# DAB_FM_Radio.net
KiCad netlist of a schematic drawn in EAGLE
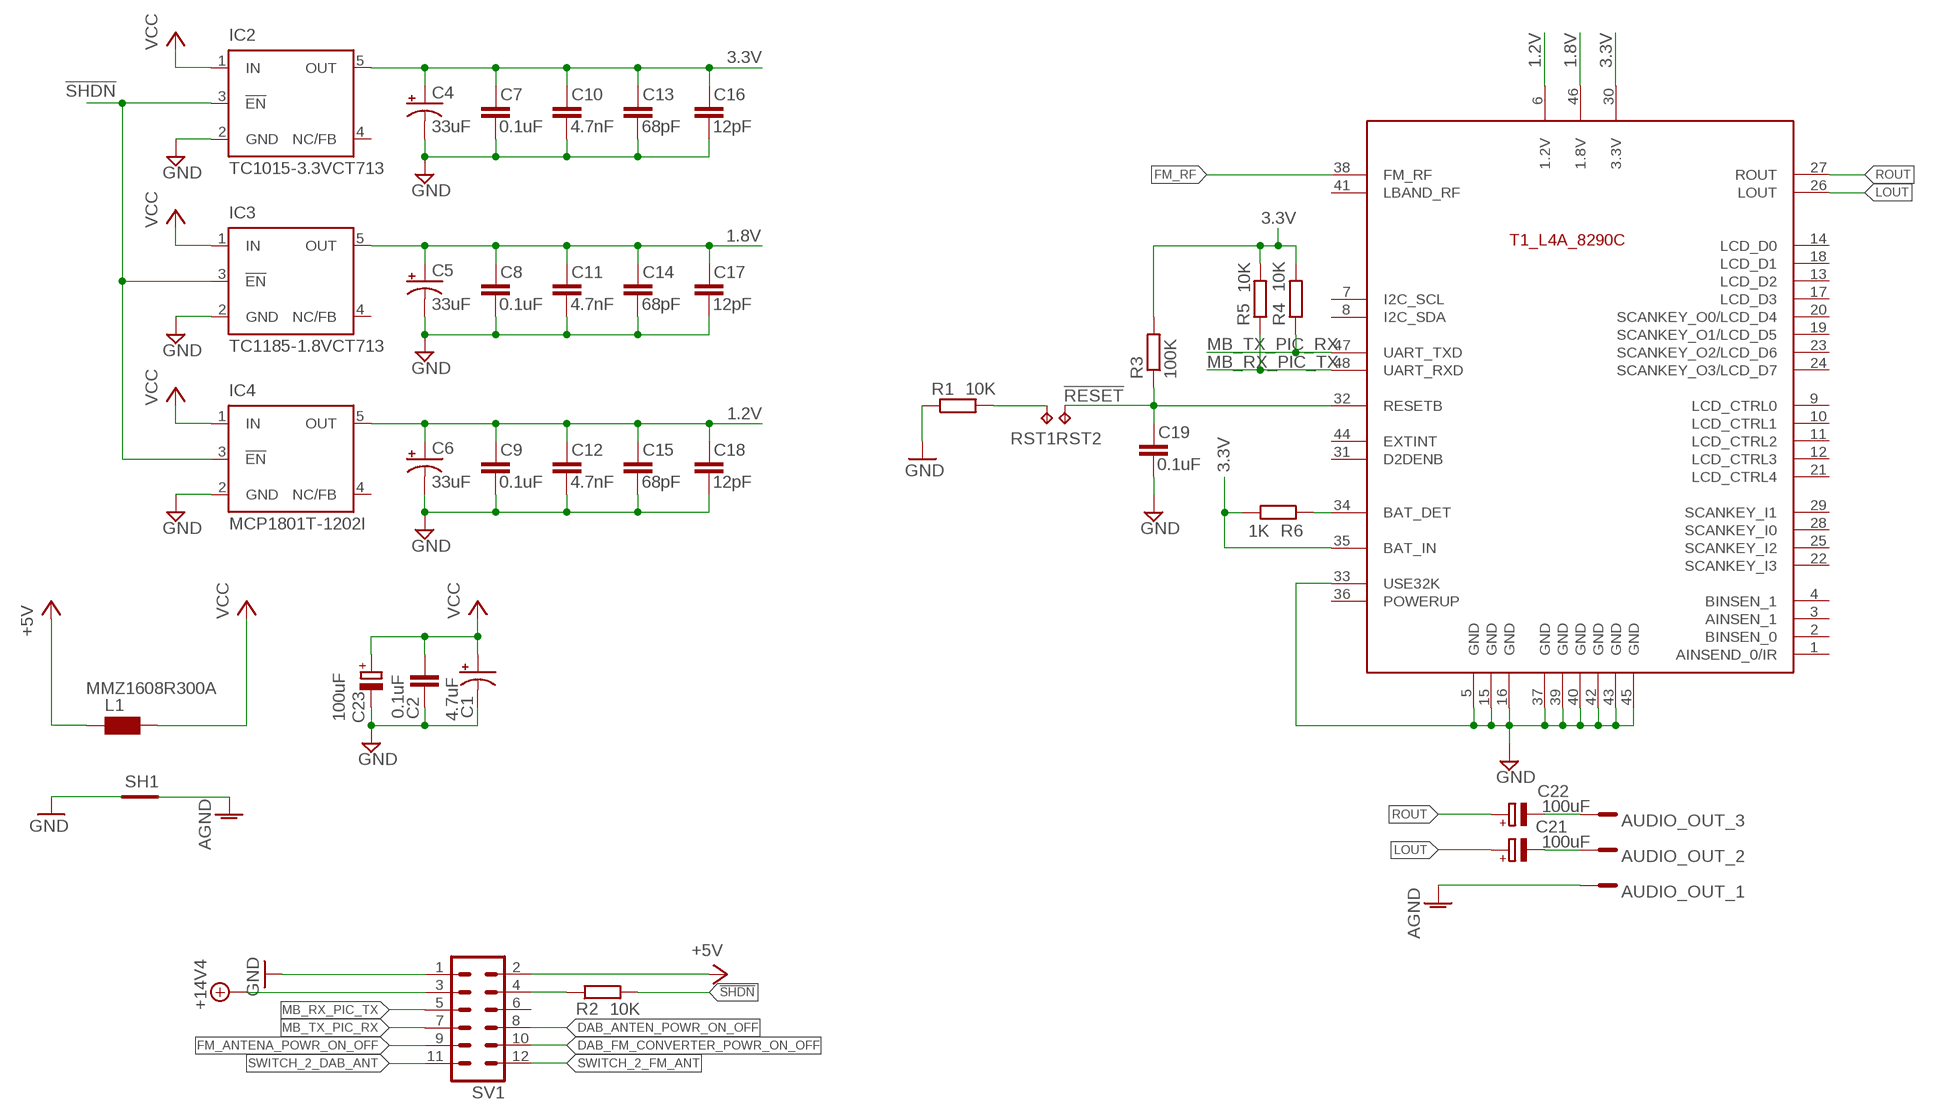
[diagram p0: schematic, sheet 1, part 1 of 2]
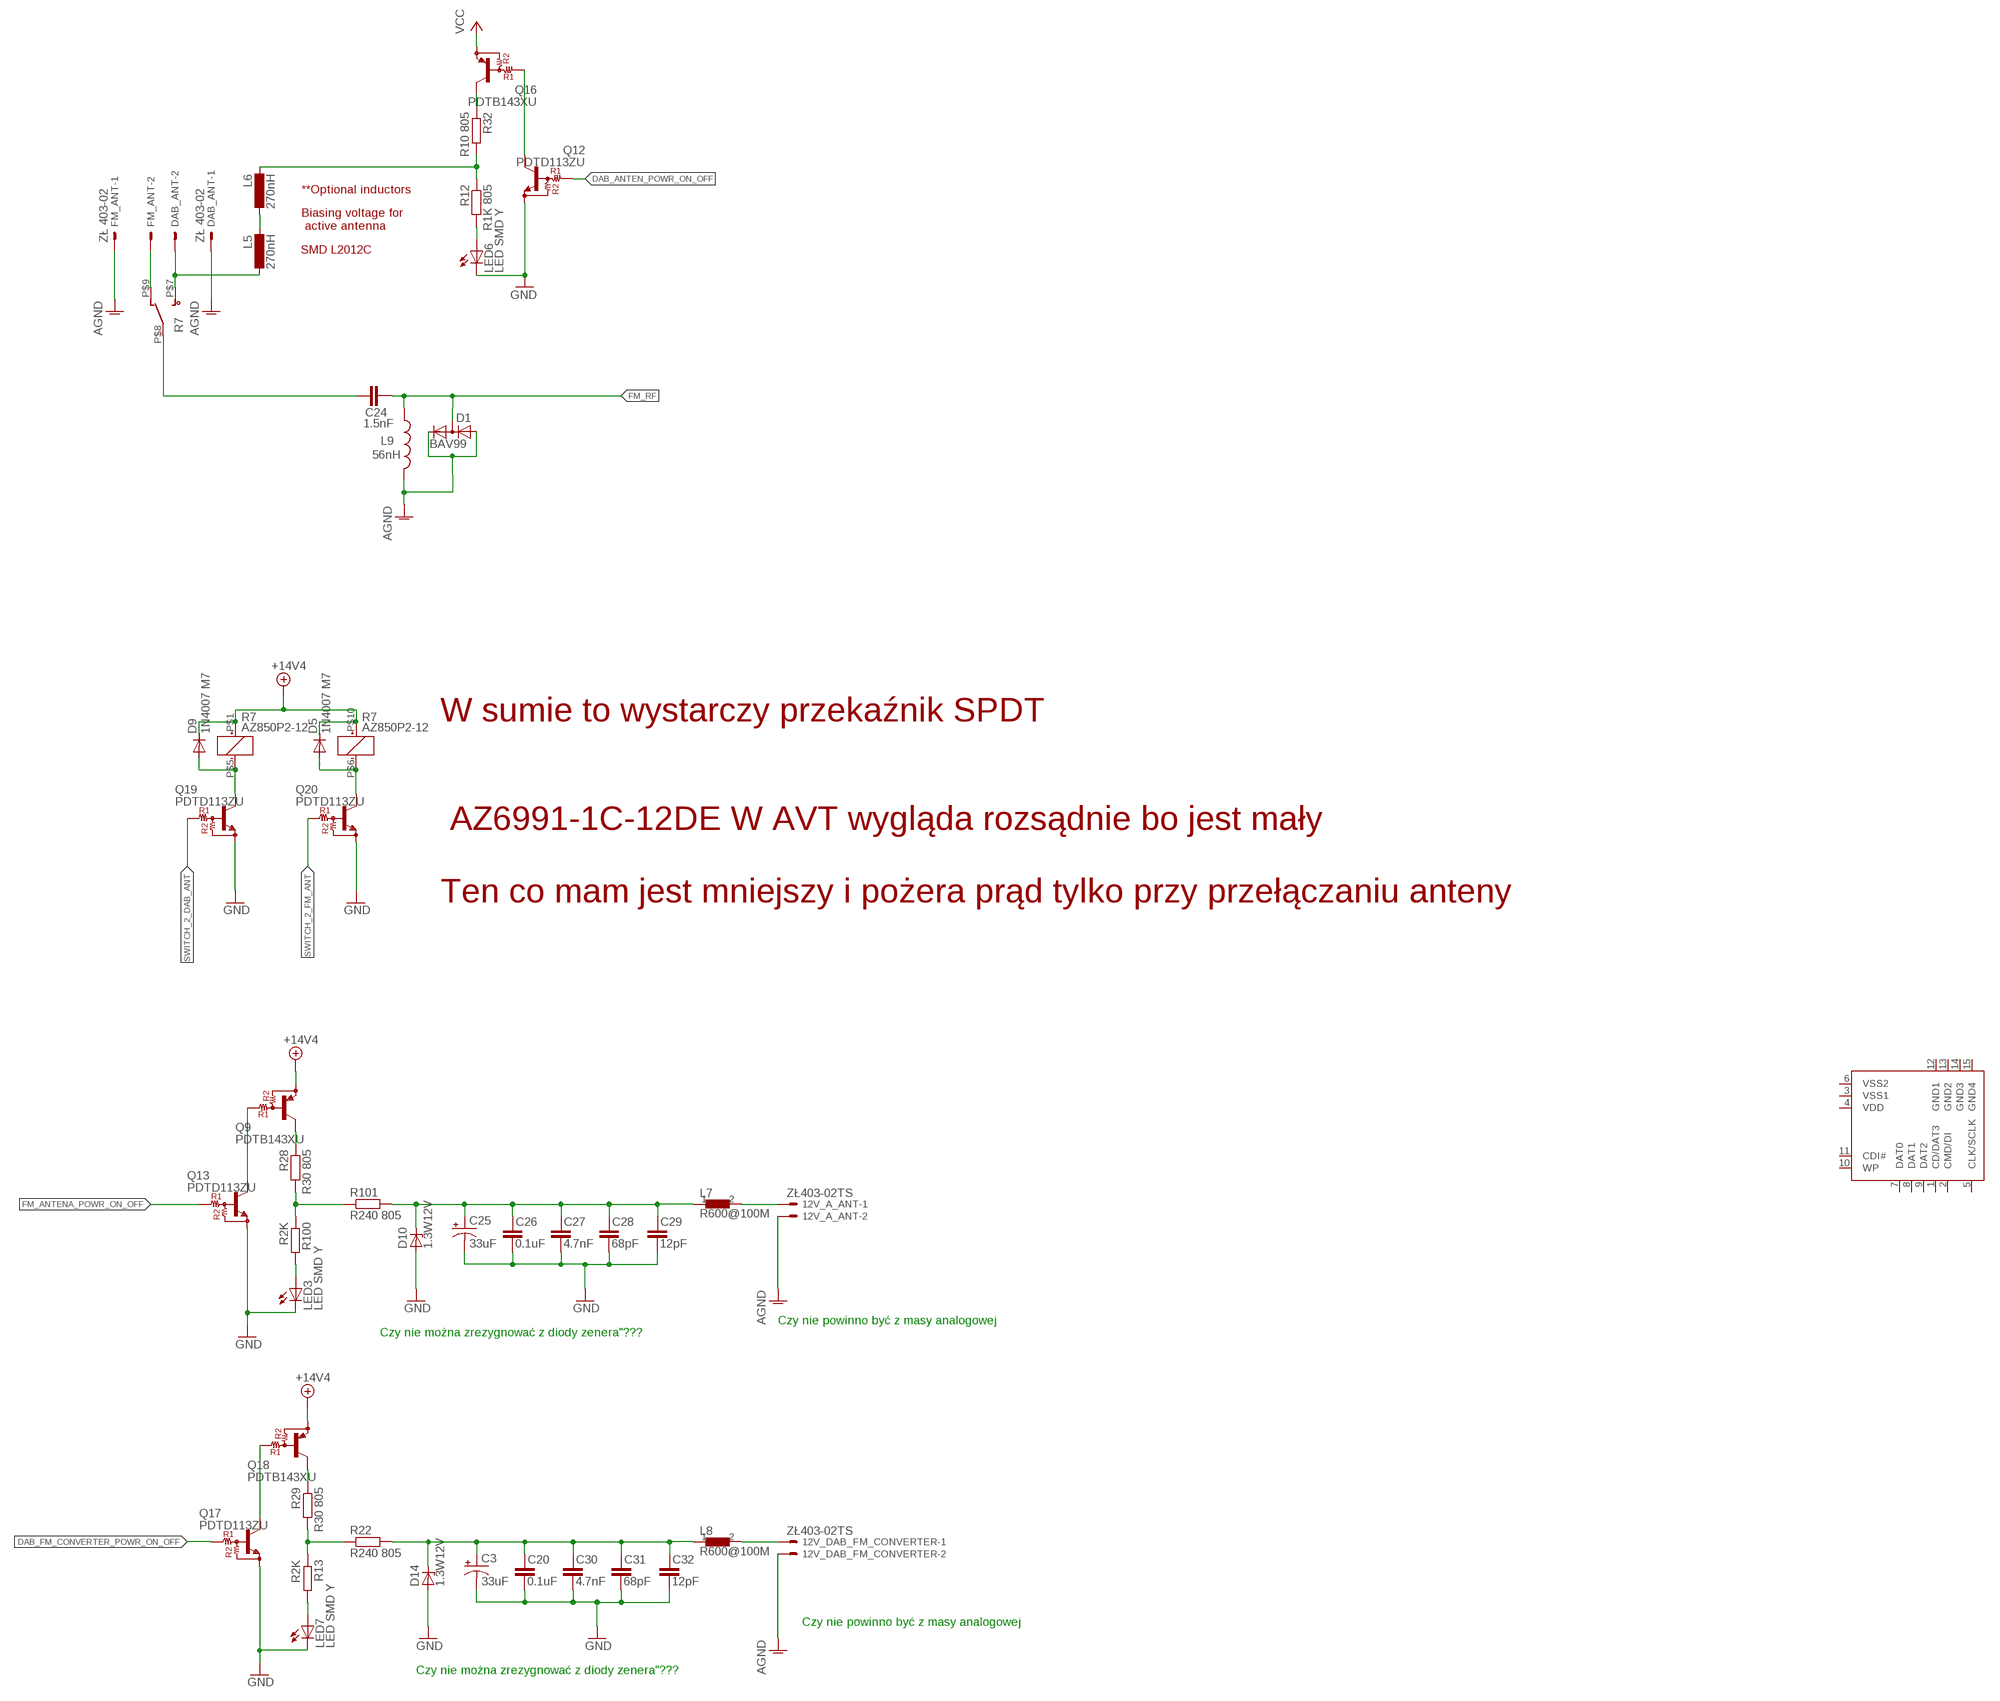
[diagram p1: schematic, sheet 1, part 2 of 2]

(export (version "E")
  (design (tool "Eeschema 10.0.6"))
  (components
    (comp (ref "12V_A_ANT")
      (value "ZŁ403-02TS")
      (footprint "eagle-import:22-23-2021")
      (fields (field (name "MF") "MOLEX") (field (name "MPN") "22-23-2021"))
      (libsource (lib "eagle-import") (part "22-23-2021"))
    )
    (comp (ref "12V_DAB_FM_CONVERTER")
      (value "ZŁ403-02TS")
      (footprint "eagle-import:22-23-2021")
      (fields (field (name "MF") "MOLEX") (field (name "MPN") "22-23-2021"))
      (libsource (lib "eagle-import") (part "22-23-2021"))
    )
    (comp (ref "AUDIO_OUT")
      (value "JST_3_PIN_B3B-PH-KS")
      (footprint "eagle-import:B3B-PH-KS")
      (libsource (lib "eagle-import") (part "JST_3_PIN_B3B-PH-KS"))
    )
    (comp (ref "C1")
      (value "4.7uF")
      (footprint "eagle-import:EIA3216")
      (libsource (lib "eagle-import") (part "CAP_POL1206"))
    )
    (comp (ref "C2")
      (value "0.1uF")
      (footprint "eagle-import:C0603")
      (libsource (lib "eagle-import") (part "C-EUC0603"))
    )
    (comp (ref "C3")
      (value "33uF")
      (footprint "eagle-import:EIA3216")
      (libsource (lib "eagle-import") (part "CAP_POL1206"))
    )
    (comp (ref "C4")
      (value "33uF")
      (footprint "eagle-import:EIA3216")
      (libsource (lib "eagle-import") (part "CAP_POL1206"))
    )
    (comp (ref "C5")
      (value "33uF")
      (footprint "eagle-import:EIA3216")
      (libsource (lib "eagle-import") (part "CAP_POL1206"))
    )
    (comp (ref "C6")
      (value "33uF")
      (footprint "eagle-import:EIA3216")
      (libsource (lib "eagle-import") (part "CAP_POL1206"))
    )
    (comp (ref "C7")
      (value "0.1uF")
      (footprint "eagle-import:C0603")
      (libsource (lib "eagle-import") (part "C-EUC0603"))
    )
    (comp (ref "C8")
      (value "0.1uF")
      (footprint "eagle-import:C0603")
      (libsource (lib "eagle-import") (part "C-EUC0603"))
    )
    (comp (ref "C9")
      (value "0.1uF")
      (footprint "eagle-import:C0603")
      (libsource (lib "eagle-import") (part "C-EUC0603"))
    )
    (comp (ref "C10")
      (value "4.7nF")
      (footprint "eagle-import:C0603")
      (libsource (lib "eagle-import") (part "C-EUC0603"))
    )
    (comp (ref "C11")
      (value "4.7nF")
      (footprint "eagle-import:C0603")
      (libsource (lib "eagle-import") (part "C-EUC0603"))
    )
    (comp (ref "C12")
      (value "4.7nF")
      (footprint "eagle-import:C0603")
      (libsource (lib "eagle-import") (part "C-EUC0603"))
    )
    (comp (ref "C13")
      (value "68pF")
      (footprint "eagle-import:C0603")
      (libsource (lib "eagle-import") (part "C-EUC0603"))
    )
    (comp (ref "C14")
      (value "68pF")
      (footprint "eagle-import:C0603")
      (libsource (lib "eagle-import") (part "C-EUC0603"))
    )
    (comp (ref "C15")
      (value "68pF")
      (footprint "eagle-import:C0603")
      (libsource (lib "eagle-import") (part "C-EUC0603"))
    )
    (comp (ref "C16")
      (value "12pF")
      (footprint "eagle-import:C0603")
      (libsource (lib "eagle-import") (part "C-EUC0603"))
    )
    (comp (ref "C17")
      (value "12pF")
      (footprint "eagle-import:C0603")
      (libsource (lib "eagle-import") (part "C-EUC0603"))
    )
    (comp (ref "C18")
      (value "12pF")
      (footprint "eagle-import:C0603")
      (libsource (lib "eagle-import") (part "C-EUC0603"))
    )
    (comp (ref "C19")
      (value "0.1uF")
      (footprint "eagle-import:C0603")
      (libsource (lib "eagle-import") (part "C-EUC0603"))
    )
    (comp (ref "C20")
      (value "0.1uF")
      (footprint "eagle-import:C0603")
      (libsource (lib "eagle-import") (part "C-EUC0603"))
    )
    (comp (ref "C21")
      (value "100uF")
      (footprint "eagle-import:PANASONIC_D")
      (libsource (lib "eagle-import") (part "CPOL-EUD"))
    )
    (comp (ref "C22")
      (value "100uF")
      (footprint "eagle-import:PANASONIC_D")
      (libsource (lib "eagle-import") (part "CPOL-EUD"))
    )
    (comp (ref "C23")
      (value "100uF")
      (footprint "eagle-import:PANASONIC_D")
      (libsource (lib "eagle-import") (part "CPOL-EUD"))
    )
    (comp (ref "C24")
      (value "1.5nF")
      (footprint "eagle-import:C0603")
      (libsource (lib "eagle-import") (part "C-EUC0603"))
    )
    (comp (ref "C25")
      (value "33uF")
      (footprint "eagle-import:EIA3216")
      (libsource (lib "eagle-import") (part "CAP_POL1206"))
    )
    (comp (ref "C26")
      (value "0.1uF")
      (footprint "eagle-import:C0603")
      (libsource (lib "eagle-import") (part "C-EUC0603"))
    )
    (comp (ref "C27")
      (value "4.7nF")
      (footprint "eagle-import:C0603")
      (libsource (lib "eagle-import") (part "C-EUC0603"))
    )
    (comp (ref "C28")
      (value "68pF")
      (footprint "eagle-import:C0603")
      (libsource (lib "eagle-import") (part "C-EUC0603"))
    )
    (comp (ref "C29")
      (value "12pF")
      (footprint "eagle-import:C0603")
      (libsource (lib "eagle-import") (part "C-EUC0603"))
    )
    (comp (ref "C30")
      (value "4.7nF")
      (footprint "eagle-import:C0603")
      (libsource (lib "eagle-import") (part "C-EUC0603"))
    )
    (comp (ref "C31")
      (value "68pF")
      (footprint "eagle-import:C0603")
      (libsource (lib "eagle-import") (part "C-EUC0603"))
    )
    (comp (ref "C32")
      (value "12pF")
      (footprint "eagle-import:C0603")
      (libsource (lib "eagle-import") (part "C-EUC0603"))
    )
    (comp (ref "D1")
      (value "BAV99")
      (footprint "eagle-import:SOT23")
      (libsource (lib "eagle-import") (part "BAV199"))
    )
    (comp (ref "D5")
      (value "1N4007 M7")
      (footprint "eagle-import:SOD-123_MINI-SMA")
      (libsource (lib "eagle-import") (part "CGRM400-G1"))
    )
    (comp (ref "D9")
      (value "1N4007 M7")
      (footprint "eagle-import:SOD-123_MINI-SMA")
      (libsource (lib "eagle-import") (part "CGRM400-G1"))
    )
    (comp (ref "D10")
      (value "1.3W12V")
      (footprint "eagle-import:ZDIO-2.5")
      (libsource (lib "eagle-import") (part "ZENER-DIODEZD-2.5"))
    )
    (comp (ref "D14")
      (value "1.3W12V")
      (footprint "eagle-import:ZDIO-2.5")
      (libsource (lib "eagle-import") (part "ZENER-DIODEZD-2.5"))
    )
    (comp (ref "DAB_ANT")
      (value "ZŁ 403-02")
      (footprint "eagle-import:6410-02")
      (fields (field (name "OC_FARNELL") "unknown") (field (name "OC_NEWARK") "unknown"))
      (libsource (lib "eagle-import") (part "22-?-0227-2021"))
    )
    (comp (ref "FM_ANT")
      (value "ZŁ 403-02")
      (footprint "eagle-import:6410-02")
      (libsource (lib "eagle-import") (part "22-?-0227-2021"))
    )
    (comp (ref "IC2")
      (value "TC1015-3.3VCT713")
      (footprint "eagle-import:SOT23-DBV")
      (fields (field (name "MF") "TEXAS INSTRUMENTS") (field (name "MPN") "TPS77001DBVT"))
      (libsource (lib "eagle-import") (part "TPS77001"))
    )
    (comp (ref "IC3")
      (value "TC1185-1.8VCT713")
      (footprint "eagle-import:SOT23-DBV")
      (fields (field (name "MF") "TEXAS INSTRUMENTS") (field (name "MPN") "TPS77001DBVT"))
      (libsource (lib "eagle-import") (part "TPS77001"))
    )
    (comp (ref "IC4")
      (value "MCP1801T-1202I")
      (footprint "eagle-import:SOT23-DBV")
      (fields (field (name "MF") "TEXAS INSTRUMENTS") (field (name "MPN") "TPS77001DBVT"))
      (libsource (lib "eagle-import") (part "TPS77001"))
    )
    (comp (ref "L1")
      (value "MMZ1608R300A")
      (footprint "eagle-import:0603")
      (libsource (lib "eagle-import") (part "WE-CBF_0603"))
    )
    (comp (ref "L5")
      (value "270nH")
      (footprint "eagle-import:L2012C")
      (libsource (lib "eagle-import") (part "L-EUL2012C"))
    )
    (comp (ref "L6")
      (value "270nH")
      (footprint "eagle-import:L2012C")
      (libsource (lib "eagle-import") (part "L-EUL2012C"))
    )
    (comp (ref "L7")
      (value "R600@100M")
      (footprint "eagle-import:R0805")
      (libsource (lib "eagle-import") (part "FERRITR0805"))
    )
    (comp (ref "L8")
      (value "R600@100M")
      (footprint "eagle-import:R0805")
      (libsource (lib "eagle-import") (part "FERRITR0805"))
    )
    (comp (ref "L9")
      (value "56nH")
      (footprint "eagle-import:0603")
      (libsource (lib "eagle-import") (part "INDUCTOR0603"))
    )
    (comp (ref "LED3")
      (value "LED SMD Y")
      (footprint "eagle-import:SMARTLED-TTW")
      (libsource (lib "eagle-import") (part "LED"))
    )
    (comp (ref "LED6")
      (value "LED SMD Y")
      (footprint "eagle-import:SMARTLED-TTW")
      (libsource (lib "eagle-import") (part "LED"))
    )
    (comp (ref "LED7")
      (value "LED SMD Y")
      (footprint "eagle-import:SMARTLED-TTW")
      (libsource (lib "eagle-import") (part "LED"))
    )
    (comp (ref "Q9")
      (value "PDTB143XU")
      (footprint "eagle-import:SOT-23")
      (fields (field (name "R1") "4.7 kOhm") (field (name "R2") "10 kOhm"))
      (libsource (lib "eagle-import") (part "PDTB143XU"))
    )
    (comp (ref "Q12")
      (value "PDTD113ZU")
      (footprint "eagle-import:SOT-23")
      (fields (field (name "R1") "1 kOhm") (field (name "R2") "10 kOhm"))
      (libsource (lib "eagle-import") (part "PDTD113ZU"))
    )
    (comp (ref "Q13")
      (value "PDTD113ZU")
      (footprint "eagle-import:SOT-23")
      (fields (field (name "R1") "1 kOhm") (field (name "R2") "10 kOhm"))
      (libsource (lib "eagle-import") (part "PDTD113ZU"))
    )
    (comp (ref "Q16")
      (value "PDTB143XU")
      (footprint "eagle-import:SOT-23")
      (fields (field (name "R1") "4.7 kOhm") (field (name "R2") "10 kOhm"))
      (libsource (lib "eagle-import") (part "PDTB143XU"))
    )
    (comp (ref "Q17")
      (value "PDTD113ZU")
      (footprint "eagle-import:SOT-23")
      (fields (field (name "R1") "1 kOhm") (field (name "R2") "10 kOhm"))
      (libsource (lib "eagle-import") (part "PDTD113ZU"))
    )
    (comp (ref "Q18")
      (value "PDTB143XU")
      (footprint "eagle-import:SOT-23")
      (fields (field (name "R1") "4.7 kOhm") (field (name "R2") "10 kOhm"))
      (libsource (lib "eagle-import") (part "PDTB143XU"))
    )
    (comp (ref "Q19")
      (value "PDTD113ZU")
      (footprint "eagle-import:SOT-23")
      (fields (field (name "R1") "1 kOhm") (field (name "R2") "10 kOhm"))
      (libsource (lib "eagle-import") (part "PDTD113ZU"))
    )
    (comp (ref "Q20")
      (value "PDTD113ZU")
      (footprint "eagle-import:SOT-23")
      (fields (field (name "R1") "1 kOhm") (field (name "R2") "10 kOhm"))
      (libsource (lib "eagle-import") (part "PDTD113ZU"))
    )
    (comp (ref "R1")
      (value "10K")
      (footprint "eagle-import:R0603")
      (libsource (lib "eagle-import") (part "R-EU_R0603"))
    )
    (comp (ref "R2")
      (value "10K")
      (footprint "eagle-import:R0603")
      (libsource (lib "eagle-import") (part "R-EU_R0603"))
    )
    (comp (ref "R3")
      (value "100K")
      (footprint "eagle-import:R0603")
      (libsource (lib "eagle-import") (part "R-EU_R0603"))
    )
    (comp (ref "R4")
      (value "10K")
      (footprint "eagle-import:R0603")
      (libsource (lib "eagle-import") (part "R-EU_R0603"))
    )
    (comp (ref "R5")
      (value "10K")
      (footprint "eagle-import:R0603")
      (libsource (lib "eagle-import") (part "R-EU_R0603"))
    )
    (comp (ref "R6")
      (value "1K")
      (footprint "eagle-import:R0603")
      (libsource (lib "eagle-import") (part "R-EU_R0603"))
    )
    (comp (ref "R7")
      (value "AZ850P2-12")
      (footprint "eagle-import:AZ850-2C")
      (libsource (lib "eagle-import") (part "AZ850P2-12"))
    )
    (comp (ref "R12")
      (value "R1K 805")
      (footprint "eagle-import:R0805")
      (libsource (lib "eagle-import") (part "R-EU_R0805"))
    )
    (comp (ref "R13")
      (value "R2K")
      (footprint "eagle-import:R0805")
      (libsource (lib "eagle-import") (part "R-EU_R0805"))
    )
    (comp (ref "R22")
      (value "R240 805")
      (footprint "eagle-import:M0805")
      (libsource (lib "eagle-import") (part "R-EU_M0805"))
    )
    (comp (ref "R28")
      (value "R30 805")
      (footprint "eagle-import:R0805")
      (libsource (lib "eagle-import") (part "R-EU_R0805"))
    )
    (comp (ref "R29")
      (value "R30 805")
      (footprint "eagle-import:R0805")
      (libsource (lib "eagle-import") (part "R-EU_R0805"))
    )
    (comp (ref "R32")
      (value "R10 805")
      (footprint "eagle-import:R0805")
      (libsource (lib "eagle-import") (part "R-EU_R0805"))
    )
    (comp (ref "R100")
      (value "R2K")
      (footprint "eagle-import:R0805")
      (libsource (lib "eagle-import") (part "R-EU_R0805"))
    )
    (comp (ref "R101")
      (value "R240 805")
      (footprint "eagle-import:M0805")
      (libsource (lib "eagle-import") (part "R-EU_M0805"))
    )
    (comp (ref "RST1")
      (value "TPB1,27")
      (footprint "eagle-import:B1,27")
      (libsource (lib "eagle-import") (part "TPB1,27"))
    )
    (comp (ref "RST2")
      (value "TPB1,27")
      (footprint "eagle-import:B1,27")
      (libsource (lib "eagle-import") (part "TPB1,27"))
    )
    (comp (ref "SH1")
      (value "SHORT-HT5")
      (footprint "eagle-import:SHORT_TOP-50")
      (libsource (lib "eagle-import") (part "SHORT-HT5"))
    )
    (comp (ref "SV1")
      (value "MA06-2")
      (footprint "eagle-import:MA06-2")
      (libsource (lib "eagle-import") (part "MA06-2"))
    )
    (comp (ref "U$1")
      (value "T1_L4A_8290C/T2_L4A_8650C")
      (footprint "eagle-import:T1_L4A")
      (libsource (lib "eagle-import") (part "T1_L4A_8290C"))
    )
    (comp (ref "U$6")
      (value "ZŁ KART SD")
      (footprint "eagle-import:SDCMF-10915W010")
      (libsource (lib "eagle-import") (part "SDCARDVAR2"))
    )
  )
  (nets
    (net (code "1") (name "+5V") (class "Default")
      (node (ref "L1") (pin "1") (pinfunction "1_1") (pintype "passive"))
      (node (ref "SV1") (pin "2") (pinfunction "2_2") (pintype "passive"))
    )
    (net (code "2") (name "+14V4") (class "Default")
      (node (ref "D5") (pin "C") (pinfunction "C_C") (pintype "passive"))
      (node (ref "D9") (pin "C") (pinfunction "C_C") (pintype "passive"))
      (node (ref "Q18") (pin "2") (pinfunction "E_2") (pintype "passive"))
      (node (ref "Q9") (pin "2") (pinfunction "E_2") (pintype "passive"))
      (node (ref "R7") (pin "P$1") (pinfunction "+_P$1") (pintype "passive"))
      (node (ref "R7") (pin "P$10") (pinfunction "+_P$10") (pintype "passive"))
      (node (ref "SV1") (pin "3") (pinfunction "3_3") (pintype "passive"))
    )
    (net (code "3") (name "/1.2V") (class "Default")
      (node (ref "C12") (pin "1") (pinfunction "1_1") (pintype "passive"))
      (node (ref "C15") (pin "1") (pinfunction "1_1") (pintype "passive"))
      (node (ref "C18") (pin "1") (pinfunction "1_1") (pintype "passive"))
      (node (ref "C6") (pin "A") (pinfunction "+_A") (pintype "passive"))
      (node (ref "C9") (pin "1") (pinfunction "1_1") (pintype "passive"))
      (node (ref "IC4") (pin "5") (pinfunction "OUT_5") (pintype "passive"))
      (node (ref "U$1") (pin "6") (pinfunction "1.2V_6") (pintype "bidirectional"))
    )
    (net (code "4") (name "/1.8V") (class "Default")
      (node (ref "C11") (pin "1") (pinfunction "1_1") (pintype "passive"))
      (node (ref "C14") (pin "1") (pinfunction "1_1") (pintype "passive"))
      (node (ref "C17") (pin "1") (pinfunction "1_1") (pintype "passive"))
      (node (ref "C5") (pin "A") (pinfunction "+_A") (pintype "passive"))
      (node (ref "C8") (pin "1") (pinfunction "1_1") (pintype "passive"))
      (node (ref "IC3") (pin "5") (pinfunction "OUT_5") (pintype "passive"))
      (node (ref "U$1") (pin "46") (pinfunction "1.8V_46") (pintype "bidirectional"))
    )
    (net (code "5") (name "/3.3V") (class "Default")
      (node (ref "C10") (pin "1") (pinfunction "1_1") (pintype "passive"))
      (node (ref "C13") (pin "1") (pinfunction "1_1") (pintype "passive"))
      (node (ref "C16") (pin "1") (pinfunction "1_1") (pintype "passive"))
      (node (ref "C4") (pin "A") (pinfunction "+_A") (pintype "passive"))
      (node (ref "C7") (pin "1") (pinfunction "1_1") (pintype "passive"))
      (node (ref "IC2") (pin "5") (pinfunction "OUT_5") (pintype "passive"))
      (node (ref "R3") (pin "2") (pinfunction "2_2") (pintype "passive"))
      (node (ref "R4") (pin "2") (pinfunction "2_2") (pintype "passive"))
      (node (ref "R5") (pin "2") (pinfunction "2_2") (pintype "passive"))
      (node (ref "R6") (pin "2") (pinfunction "2_2") (pintype "passive"))
      (node (ref "U$1") (pin "30") (pinfunction "3.3V_30") (pintype "bidirectional"))
      (node (ref "U$1") (pin "35") (pinfunction "BAT_IN_35") (pintype "bidirectional"))
    )
    (net (code "6") (name "/GND1") (class "Default")
      (node (ref "U$6") (pin "12") (pinfunction "GND1_12") (pintype "power_in"))
    )
    (net (code "7") (name "/GND2") (class "Default")
      (node (ref "U$6") (pin "13") (pinfunction "GND2_13") (pintype "power_in"))
    )
    (net (code "8") (name "/GND3") (class "Default")
      (node (ref "U$6") (pin "14") (pinfunction "GND3_14") (pintype "power_in"))
    )
    (net (code "9") (name "/GND4") (class "Default")
      (node (ref "U$6") (pin "15") (pinfunction "GND4_15") (pintype "power_in"))
    )
    (net (code "10") (name "/VDD") (class "Default")
      (node (ref "U$6") (pin "4") (pinfunction "VDD_4") (pintype "power_in"))
    )
    (net (code "11") (name "/VSS1") (class "Default")
      (node (ref "U$6") (pin "3") (pinfunction "VSS1_3") (pintype "power_in"))
    )
    (net (code "12") (name "/VSS2") (class "Default")
      (node (ref "U$6") (pin "6") (pinfunction "VSS2_6") (pintype "power_in"))
    )
    (net (code "13") (name "/~{RESET}") (class "Default")
      (node (ref "C19") (pin "1") (pinfunction "1_1") (pintype "passive"))
      (node (ref "R3") (pin "1") (pinfunction "1_1") (pintype "passive"))
      (node (ref "RST2") (pin "TP") (pinfunction "TP_TP") (pintype "input"))
      (node (ref "U$1") (pin "32") (pinfunction "RESETB_32") (pintype "bidirectional"))
    )
    (net (code "14") (name "/~{SHDN}") (class "Default")
      (node (ref "IC2") (pin "3") (pinfunction "~{EN}_3") (pintype "input"))
      (node (ref "IC3") (pin "3") (pinfunction "~{EN}_3") (pintype "input"))
      (node (ref "IC4") (pin "3") (pinfunction "~{EN}_3") (pintype "input"))
      (node (ref "R2") (pin "2") (pinfunction "2_2") (pintype "passive"))
    )
    (net (code "15") (name "AGND") (class "Default")
      (node (ref "12V_A_ANT") (pin "2") (pinfunction "S_2") (pintype "passive"))
      (node (ref "12V_DAB_FM_CONVERTER") (pin "2") (pinfunction "S_2") (pintype "passive"))
      (node (ref "AUDIO_OUT") (pin "P$1") (pinfunction "P$1_P$1") (pintype "bidirectional"))
      (node (ref "D1") (pin "1") (pinfunction "A_1") (pintype "passive"))
      (node (ref "D1") (pin "2") (pinfunction "C_2") (pintype "passive"))
      (node (ref "DAB_ANT") (pin "1") (pinfunction "S_1") (pintype "passive"))
      (node (ref "FM_ANT") (pin "1") (pinfunction "S_1") (pintype "passive"))
      (node (ref "L9") (pin "2") (pinfunction "2_2") (pintype "passive"))
      (node (ref "SH1") (pin "2") (pinfunction "P$2_2") (pintype "bidirectional"))
    )
    (net (code "16") (name "DAB_ANTEN_POWR_ON_OFF") (class "Default")
      (node (ref "Q12") (pin "1") (pinfunction "B_1") (pintype "passive"))
      (node (ref "SV1") (pin "8") (pinfunction "8_8") (pintype "passive"))
    )
    (net (code "17") (name "DAB_FM_CONVERTER_POWR_ON_OFF") (class "Default")
      (node (ref "Q17") (pin "1") (pinfunction "B_1") (pintype "passive"))
      (node (ref "SV1") (pin "10") (pinfunction "10_10") (pintype "passive"))
    )
    (net (code "18") (name "FM_ANTENA_POWR_ON_OFF") (class "Default")
      (node (ref "Q13") (pin "1") (pinfunction "B_1") (pintype "passive"))
      (node (ref "SV1") (pin "9") (pinfunction "9_9") (pintype "passive"))
    )
    (net (code "19") (name "FM_RF") (class "Default")
      (node (ref "C24") (pin "2") (pinfunction "2_2") (pintype "passive"))
      (node (ref "D1") (pin "3") (pinfunction "AC_3") (pintype "passive"))
      (node (ref "L9") (pin "1") (pinfunction "1_1") (pintype "passive"))
      (node (ref "U$1") (pin "38") (pinfunction "FM_RF_38") (pintype "bidirectional"))
    )
    (net (code "20") (name "GND") (class "Default")
      (node (ref "C1") (pin "C") (pinfunction "-_C") (pintype "passive"))
      (node (ref "C10") (pin "2") (pinfunction "2_2") (pintype "passive"))
      (node (ref "C11") (pin "2") (pinfunction "2_2") (pintype "passive"))
      (node (ref "C12") (pin "2") (pinfunction "2_2") (pintype "passive"))
      (node (ref "C13") (pin "2") (pinfunction "2_2") (pintype "passive"))
      (node (ref "C14") (pin "2") (pinfunction "2_2") (pintype "passive"))
      (node (ref "C15") (pin "2") (pinfunction "2_2") (pintype "passive"))
      (node (ref "C16") (pin "2") (pinfunction "2_2") (pintype "passive"))
      (node (ref "C17") (pin "2") (pinfunction "2_2") (pintype "passive"))
      (node (ref "C18") (pin "2") (pinfunction "2_2") (pintype "passive"))
      (node (ref "C19") (pin "2") (pinfunction "2_2") (pintype "passive"))
      (node (ref "C2") (pin "2") (pinfunction "2_2") (pintype "passive"))
      (node (ref "C20") (pin "2") (pinfunction "2_2") (pintype "passive"))
      (node (ref "C23") (pin "-") (pinfunction "-_-") (pintype "passive"))
      (node (ref "C25") (pin "C") (pinfunction "-_C") (pintype "passive"))
      (node (ref "C26") (pin "2") (pinfunction "2_2") (pintype "passive"))
      (node (ref "C27") (pin "2") (pinfunction "2_2") (pintype "passive"))
      (node (ref "C28") (pin "2") (pinfunction "2_2") (pintype "passive"))
      (node (ref "C29") (pin "2") (pinfunction "2_2") (pintype "passive"))
      (node (ref "C3") (pin "C") (pinfunction "-_C") (pintype "passive"))
      (node (ref "C30") (pin "2") (pinfunction "2_2") (pintype "passive"))
      (node (ref "C31") (pin "2") (pinfunction "2_2") (pintype "passive"))
      (node (ref "C32") (pin "2") (pinfunction "2_2") (pintype "passive"))
      (node (ref "C4") (pin "C") (pinfunction "-_C") (pintype "passive"))
      (node (ref "C5") (pin "C") (pinfunction "-_C") (pintype "passive"))
      (node (ref "C6") (pin "C") (pinfunction "-_C") (pintype "passive"))
      (node (ref "C7") (pin "2") (pinfunction "2_2") (pintype "passive"))
      (node (ref "C8") (pin "2") (pinfunction "2_2") (pintype "passive"))
      (node (ref "C9") (pin "2") (pinfunction "2_2") (pintype "passive"))
      (node (ref "D10") (pin "A") (pinfunction "A_A") (pintype "passive"))
      (node (ref "D14") (pin "A") (pinfunction "A_A") (pintype "passive"))
      (node (ref "IC2") (pin "2") (pinfunction "GND_2") (pintype "power_in"))
      (node (ref "IC3") (pin "2") (pinfunction "GND_2") (pintype "power_in"))
      (node (ref "IC4") (pin "2") (pinfunction "GND_2") (pintype "power_in"))
      (node (ref "LED3") (pin "C@1") (pinfunction "C_C@1") (pintype "passive"))
      (node (ref "LED6") (pin "C@1") (pinfunction "C_C@1") (pintype "passive"))
      (node (ref "LED7") (pin "C@1") (pinfunction "C_C@1") (pintype "passive"))
      (node (ref "Q12") (pin "2") (pinfunction "E_2") (pintype "passive"))
      (node (ref "Q13") (pin "2") (pinfunction "E_2") (pintype "passive"))
      (node (ref "Q17") (pin "2") (pinfunction "E_2") (pintype "passive"))
      (node (ref "Q19") (pin "2") (pinfunction "E_2") (pintype "passive"))
      (node (ref "Q20") (pin "2") (pinfunction "E_2") (pintype "passive"))
      (node (ref "R1") (pin "1") (pinfunction "1_1") (pintype "passive"))
      (node (ref "SH1") (pin "1") (pinfunction "P$1_1") (pintype "bidirectional"))
      (node (ref "SV1") (pin "1") (pinfunction "1_1") (pintype "passive"))
      (node (ref "U$1") (pin "15") (pinfunction "GND_15") (pintype "bidirectional"))
      (node (ref "U$1") (pin "16") (pinfunction "GND_16") (pintype "bidirectional"))
      (node (ref "U$1") (pin "33") (pinfunction "USE32K_33") (pintype "bidirectional"))
      (node (ref "U$1") (pin "37") (pinfunction "GND_37") (pintype "bidirectional"))
      (node (ref "U$1") (pin "39") (pinfunction "GND_39") (pintype "bidirectional"))
      (node (ref "U$1") (pin "40") (pinfunction "GND_40") (pintype "bidirectional"))
      (node (ref "U$1") (pin "42") (pinfunction "GND_42") (pintype "bidirectional"))
      (node (ref "U$1") (pin "43") (pinfunction "GND_43") (pintype "bidirectional"))
      (node (ref "U$1") (pin "45") (pinfunction "GND_45") (pintype "bidirectional"))
      (node (ref "U$1") (pin "5") (pinfunction "GND_5") (pintype "bidirectional"))
    )
    (net (code "21") (name "LOUT") (class "Default")
      (node (ref "C21") (pin "+") (pinfunction "+_+") (pintype "passive"))
      (node (ref "U$1") (pin "26") (pinfunction "LOUT_26") (pintype "bidirectional"))
    )
    (net (code "22") (name "MB_RX_PIC_TX") (class "Default")
      (node (ref "R5") (pin "1") (pinfunction "1_1") (pintype "passive"))
      (node (ref "SV1") (pin "5") (pinfunction "5_5") (pintype "passive"))
      (node (ref "U$1") (pin "48") (pinfunction "UART_RXD_48") (pintype "bidirectional"))
    )
    (net (code "23") (name "MB_TX_PIC_RX") (class "Default")
      (node (ref "R4") (pin "1") (pinfunction "1_1") (pintype "passive"))
      (node (ref "SV1") (pin "7") (pinfunction "7_7") (pintype "passive"))
      (node (ref "U$1") (pin "47") (pinfunction "UART_TXD_47") (pintype "bidirectional"))
    )
    (net (code "24") (name "Net-(12V_A_ANTA-S)") (class "Default")
      (node (ref "12V_A_ANT") (pin "1") (pinfunction "S_1") (pintype "passive"))
      (node (ref "L7") (pin "2") (pinfunction "2_2") (pintype "passive"))
    )
    (net (code "25") (name "Net-(12V_DAB_FM_CONVERTERA-S)") (class "Default")
      (node (ref "12V_DAB_FM_CONVERTER") (pin "1") (pinfunction "S_1") (pintype "passive"))
      (node (ref "L8") (pin "2") (pinfunction "2_2") (pintype "passive"))
    )
    (net (code "26") (name "Net-(AUDIO_OUTB-P$1)") (class "Default")
      (node (ref "AUDIO_OUT") (pin "P$2") (pinfunction "P$1_P$2") (pintype "bidirectional"))
      (node (ref "C21") (pin "-") (pinfunction "-_-") (pintype "passive"))
    )
    (net (code "27") (name "Net-(AUDIO_OUTC-P$1)") (class "Default")
      (node (ref "AUDIO_OUT") (pin "P$3") (pinfunction "P$1_P$3") (pintype "bidirectional"))
      (node (ref "C22") (pin "-") (pinfunction "-_-") (pintype "passive"))
    )
    (net (code "28") (name "Net-(C3-+)") (class "Default")
      (node (ref "C20") (pin "1") (pinfunction "1_1") (pintype "passive"))
      (node (ref "C3") (pin "A") (pinfunction "+_A") (pintype "passive"))
      (node (ref "C30") (pin "1") (pinfunction "1_1") (pintype "passive"))
      (node (ref "C31") (pin "1") (pinfunction "1_1") (pintype "passive"))
      (node (ref "C32") (pin "1") (pinfunction "1_1") (pintype "passive"))
      (node (ref "D14") (pin "C") (pinfunction "C_C") (pintype "passive"))
      (node (ref "L8") (pin "1") (pinfunction "1_1") (pintype "passive"))
      (node (ref "R22") (pin "2") (pinfunction "2_2") (pintype "passive"))
    )
    (net (code "29") (name "Net-(C25-+)") (class "Default")
      (node (ref "C25") (pin "A") (pinfunction "+_A") (pintype "passive"))
      (node (ref "C26") (pin "1") (pinfunction "1_1") (pintype "passive"))
      (node (ref "C27") (pin "1") (pinfunction "1_1") (pintype "passive"))
      (node (ref "C28") (pin "1") (pinfunction "1_1") (pintype "passive"))
      (node (ref "C29") (pin "1") (pinfunction "1_1") (pintype "passive"))
      (node (ref "D10") (pin "C") (pinfunction "C_C") (pintype "passive"))
      (node (ref "L7") (pin "1") (pinfunction "1_1") (pintype "passive"))
      (node (ref "R101") (pin "2") (pinfunction "2_2") (pintype "passive"))
    )
    (net (code "30") (name "Net-(DAB_ANTB-S)") (class "Default")
      (node (ref "DAB_ANT") (pin "2") (pinfunction "S_2") (pintype "passive"))
      (node (ref "L5") (pin "2") (pinfunction "2_2") (pintype "passive"))
      (node (ref "R7") (pin "P$7") (pinfunction "6_P$7") (pintype "passive"))
    )
    (net (code "31") (name "Net-(FM_ANTB-S)") (class "Default")
      (node (ref "FM_ANT") (pin "2") (pinfunction "S_2") (pintype "passive"))
      (node (ref "R7") (pin "P$9") (pinfunction "4_P$9") (pintype "passive"))
    )
    (net (code "32") (name "Net-(L5-Pad1)") (class "Default")
      (node (ref "L5") (pin "1") (pinfunction "1_1") (pintype "passive"))
      (node (ref "L6") (pin "2") (pinfunction "2_2") (pintype "passive"))
    )
    (net (code "33") (name "Net-(L6-Pad1)") (class "Default")
      (node (ref "L6") (pin "1") (pinfunction "1_1") (pintype "passive"))
      (node (ref "R12") (pin "1") (pinfunction "1_1") (pintype "passive"))
      (node (ref "R32") (pin "2") (pinfunction "2_2") (pintype "passive"))
    )
    (net (code "34") (name "Net-(LED3-A)") (class "Default")
      (node (ref "LED3") (pin "A@1") (pinfunction "A_A@1") (pintype "passive"))
      (node (ref "R100") (pin "2") (pinfunction "2_2") (pintype "passive"))
    )
    (net (code "35") (name "Net-(LED6-A)") (class "Default")
      (node (ref "LED6") (pin "A@1") (pinfunction "A_A@1") (pintype "passive"))
      (node (ref "R12") (pin "2") (pinfunction "2_2") (pintype "passive"))
    )
    (net (code "36") (name "Net-(LED7-A)") (class "Default")
      (node (ref "LED7") (pin "A@1") (pinfunction "A_A@1") (pintype "passive"))
      (node (ref "R13") (pin "2") (pinfunction "2_2") (pintype "passive"))
    )
    (net (code "37") (name "Net-(Q9-C)") (class "Default")
      (node (ref "Q9") (pin "3") (pinfunction "C_3") (pintype "passive"))
      (node (ref "R28") (pin "1") (pinfunction "1_1") (pintype "passive"))
    )
    (net (code "38") (name "Net-(Q12-C)") (class "Default")
      (node (ref "Q12") (pin "3") (pinfunction "C_3") (pintype "passive"))
      (node (ref "Q16") (pin "1") (pinfunction "B_1") (pintype "passive"))
    )
    (net (code "39") (name "Net-(Q13-C)") (class "Default")
      (node (ref "Q13") (pin "3") (pinfunction "C_3") (pintype "passive"))
      (node (ref "Q9") (pin "1") (pinfunction "B_1") (pintype "passive"))
    )
    (net (code "40") (name "Net-(Q16-C)") (class "Default")
      (node (ref "Q16") (pin "3") (pinfunction "C_3") (pintype "passive"))
      (node (ref "R32") (pin "1") (pinfunction "1_1") (pintype "passive"))
    )
    (net (code "41") (name "Net-(Q17-C)") (class "Default")
      (node (ref "Q17") (pin "3") (pinfunction "C_3") (pintype "passive"))
      (node (ref "Q18") (pin "1") (pinfunction "B_1") (pintype "passive"))
    )
    (net (code "42") (name "Net-(Q18-C)") (class "Default")
      (node (ref "Q18") (pin "3") (pinfunction "C_3") (pintype "passive"))
      (node (ref "R29") (pin "1") (pinfunction "1_1") (pintype "passive"))
    )
    (net (code "43") (name "Net-(Q19-C)") (class "Default")
      (node (ref "D9") (pin "A") (pinfunction "A_A") (pintype "passive"))
      (node (ref "Q19") (pin "3") (pinfunction "C_3") (pintype "passive"))
      (node (ref "R7") (pin "P$5") (pinfunction "-_P$5") (pintype "passive"))
    )
    (net (code "44") (name "Net-(Q20-C)") (class "Default")
      (node (ref "D5") (pin "A") (pinfunction "A_A") (pintype "passive"))
      (node (ref "Q20") (pin "3") (pinfunction "C_3") (pintype "passive"))
      (node (ref "R7") (pin "P$6") (pinfunction "-_P$6") (pintype "passive"))
    )
    (net (code "45") (name "Net-(R1-Pad2)") (class "Default")
      (node (ref "R1") (pin "2") (pinfunction "2_2") (pintype "passive"))
      (node (ref "RST1") (pin "TP") (pinfunction "TP_TP") (pintype "input"))
    )
    (net (code "46") (name "Net-(R2-Pad1)") (class "Default")
      (node (ref "R2") (pin "1") (pinfunction "1_1") (pintype "passive"))
      (node (ref "SV1") (pin "4") (pinfunction "4_4") (pintype "passive"))
    )
    (net (code "47") (name "Net-(R7B-5)") (class "Default")
      (node (ref "C24") (pin "1") (pinfunction "1_1") (pintype "passive"))
      (node (ref "R7") (pin "P$8") (pinfunction "5_P$8") (pintype "passive"))
    )
    (net (code "48") (name "Net-(R13-Pad1)") (class "Default")
      (node (ref "R13") (pin "1") (pinfunction "1_1") (pintype "passive"))
      (node (ref "R22") (pin "1") (pinfunction "1_1") (pintype "passive"))
      (node (ref "R29") (pin "2") (pinfunction "2_2") (pintype "passive"))
    )
    (net (code "49") (name "Net-(R100-Pad1)") (class "Default")
      (node (ref "R100") (pin "1") (pinfunction "1_1") (pintype "passive"))
      (node (ref "R101") (pin "1") (pinfunction "1_1") (pintype "passive"))
      (node (ref "R28") (pin "2") (pinfunction "2_2") (pintype "passive"))
    )
    (net (code "50") (name "Net-(U$1-BAT_DET)") (class "Default")
      (node (ref "R6") (pin "1") (pinfunction "1_1") (pintype "passive"))
      (node (ref "U$1") (pin "34") (pinfunction "BAT_DET_34") (pintype "bidirectional"))
    )
    (net (code "51") (name "ROUT") (class "Default")
      (node (ref "C22") (pin "+") (pinfunction "+_+") (pintype "passive"))
      (node (ref "U$1") (pin "27") (pinfunction "ROUT_27") (pintype "bidirectional"))
    )
    (net (code "52") (name "SWITCH_2_DAB_ANT") (class "Default")
      (node (ref "Q19") (pin "1") (pinfunction "B_1") (pintype "passive"))
      (node (ref "SV1") (pin "11") (pinfunction "11_11") (pintype "passive"))
    )
    (net (code "53") (name "SWITCH_2_FM_ANT") (class "Default")
      (node (ref "Q20") (pin "1") (pinfunction "B_1") (pintype "passive"))
      (node (ref "SV1") (pin "12") (pinfunction "12_12") (pintype "passive"))
    )
    (net (code "54") (name "VCC") (class "Default")
      (node (ref "C1") (pin "A") (pinfunction "+_A") (pintype "passive"))
      (node (ref "C2") (pin "1") (pinfunction "1_1") (pintype "passive"))
      (node (ref "C23") (pin "+") (pinfunction "+_+") (pintype "passive"))
      (node (ref "IC2") (pin "1") (pinfunction "IN_1") (pintype "input"))
      (node (ref "IC3") (pin "1") (pinfunction "IN_1") (pintype "input"))
      (node (ref "IC4") (pin "1") (pinfunction "IN_1") (pintype "input"))
      (node (ref "L1") (pin "2") (pinfunction "2_2") (pintype "passive"))
      (node (ref "Q16") (pin "2") (pinfunction "E_2") (pintype "passive"))
    )
    (net (code "55") (name "unconnected-(IC2-NC{slash}FB-Pad4)") (class "Default")
      (node (ref "IC2") (pin "4") (pinfunction "NC/FB_4") (pintype "passive"))
    )
    (net (code "56") (name "unconnected-(IC3-NC{slash}FB-Pad4)") (class "Default")
      (node (ref "IC3") (pin "4") (pinfunction "NC/FB_4") (pintype "passive"))
    )
    (net (code "57") (name "unconnected-(IC4-NC{slash}FB-Pad4)") (class "Default")
      (node (ref "IC4") (pin "4") (pinfunction "NC/FB_4") (pintype "passive"))
    )
    (net (code "58") (name "unconnected-(SV1-Pad6)") (class "Default")
      (node (ref "SV1") (pin "6") (pinfunction "6_6") (pintype "passive"))
    )
    (net (code "59") (name "unconnected-(U$1-AINSEND_0{slash}IR-Pad1)") (class "Default")
      (node (ref "U$1") (pin "1") (pinfunction "AINSEND_0/IR_1") (pintype "bidirectional"))
    )
    (net (code "60") (name "unconnected-(U$1-AINSEN_1-Pad3)") (class "Default")
      (node (ref "U$1") (pin "3") (pinfunction "AINSEN_1_3") (pintype "bidirectional"))
    )
    (net (code "61") (name "unconnected-(U$1-BINSEN_0-Pad2)") (class "Default")
      (node (ref "U$1") (pin "2") (pinfunction "BINSEN_0_2") (pintype "bidirectional"))
    )
    (net (code "62") (name "unconnected-(U$1-BINSEN_1-Pad4)") (class "Default")
      (node (ref "U$1") (pin "4") (pinfunction "BINSEN_1_4") (pintype "bidirectional"))
    )
    (net (code "63") (name "unconnected-(U$1-D2DENB-Pad31)") (class "Default")
      (node (ref "U$1") (pin "31") (pinfunction "D2DENB_31") (pintype "bidirectional"))
    )
    (net (code "64") (name "unconnected-(U$1-EXTINT-Pad44)") (class "Default")
      (node (ref "U$1") (pin "44") (pinfunction "EXTINT_44") (pintype "bidirectional"))
    )
    (net (code "65") (name "unconnected-(U$1-I2C_SCL-Pad7)") (class "Default")
      (node (ref "U$1") (pin "7") (pinfunction "I2C_SCL_7") (pintype "bidirectional"))
    )
    (net (code "66") (name "unconnected-(U$1-I2C_SDA-Pad8)") (class "Default")
      (node (ref "U$1") (pin "8") (pinfunction "I2C_SDA_8") (pintype "bidirectional"))
    )
    (net (code "67") (name "unconnected-(U$1-LBAND_RF-Pad41)") (class "Default")
      (node (ref "U$1") (pin "41") (pinfunction "LBAND_RF_41") (pintype "bidirectional"))
    )
    (net (code "68") (name "unconnected-(U$1-LCD_CTRL0-Pad9)") (class "Default")
      (node (ref "U$1") (pin "9") (pinfunction "LCD_CTRL0_9") (pintype "bidirectional"))
    )
    (net (code "69") (name "unconnected-(U$1-LCD_CTRL1-Pad10)") (class "Default")
      (node (ref "U$1") (pin "10") (pinfunction "LCD_CTRL1_10") (pintype "bidirectional"))
    )
    (net (code "70") (name "unconnected-(U$1-LCD_CTRL2-Pad11)") (class "Default")
      (node (ref "U$1") (pin "11") (pinfunction "LCD_CTRL2_11") (pintype "bidirectional"))
    )
    (net (code "71") (name "unconnected-(U$1-LCD_CTRL3-Pad12)") (class "Default")
      (node (ref "U$1") (pin "12") (pinfunction "LCD_CTRL3_12") (pintype "bidirectional"))
    )
    (net (code "72") (name "unconnected-(U$1-LCD_CTRL4-Pad21)") (class "Default")
      (node (ref "U$1") (pin "21") (pinfunction "LCD_CTRL4_21") (pintype "bidirectional"))
    )
    (net (code "73") (name "unconnected-(U$1-LCD_D0-Pad14)") (class "Default")
      (node (ref "U$1") (pin "14") (pinfunction "LCD_D0_14") (pintype "bidirectional"))
    )
    (net (code "74") (name "unconnected-(U$1-LCD_D1-Pad18)") (class "Default")
      (node (ref "U$1") (pin "18") (pinfunction "LCD_D1_18") (pintype "bidirectional"))
    )
    (net (code "75") (name "unconnected-(U$1-LCD_D2-Pad13)") (class "Default")
      (node (ref "U$1") (pin "13") (pinfunction "LCD_D2_13") (pintype "bidirectional"))
    )
    (net (code "76") (name "unconnected-(U$1-LCD_D3-Pad17)") (class "Default")
      (node (ref "U$1") (pin "17") (pinfunction "LCD_D3_17") (pintype "bidirectional"))
    )
    (net (code "77") (name "unconnected-(U$1-POWERUP-Pad36)") (class "Default")
      (node (ref "U$1") (pin "36") (pinfunction "POWERUP_36") (pintype "bidirectional"))
    )
    (net (code "78") (name "unconnected-(U$1-SCANKEY_I0-Pad28)") (class "Default")
      (node (ref "U$1") (pin "28") (pinfunction "SCANKEY_I0_28") (pintype "bidirectional"))
    )
    (net (code "79") (name "unconnected-(U$1-SCANKEY_I1-Pad29)") (class "Default")
      (node (ref "U$1") (pin "29") (pinfunction "SCANKEY_I1_29") (pintype "bidirectional"))
    )
    (net (code "80") (name "unconnected-(U$1-SCANKEY_I2-Pad25)") (class "Default")
      (node (ref "U$1") (pin "25") (pinfunction "SCANKEY_I2_25") (pintype "bidirectional"))
    )
    (net (code "81") (name "unconnected-(U$1-SCANKEY_I3-Pad22)") (class "Default")
      (node (ref "U$1") (pin "22") (pinfunction "SCANKEY_I3_22") (pintype "bidirectional"))
    )
    (net (code "82") (name "unconnected-(U$1-SCANKEY_O0{slash}LCD_D4-Pad20)") (class "Default")
      (node (ref "U$1") (pin "20") (pinfunction "SCANKEY_O0/LCD_D4_20") (pintype "bidirectional"))
    )
    (net (code "83") (name "unconnected-(U$1-SCANKEY_O1{slash}LCD_D5-Pad19)") (class "Default")
      (node (ref "U$1") (pin "19") (pinfunction "SCANKEY_O1/LCD_D5_19") (pintype "bidirectional"))
    )
    (net (code "84") (name "unconnected-(U$1-SCANKEY_O2{slash}LCD_D6-Pad23)") (class "Default")
      (node (ref "U$1") (pin "23") (pinfunction "SCANKEY_O2/LCD_D6_23") (pintype "bidirectional"))
    )
    (net (code "85") (name "unconnected-(U$1-SCANKEY_O3{slash}LCD_D7-Pad24)") (class "Default")
      (node (ref "U$1") (pin "24") (pinfunction "SCANKEY_O3/LCD_D7_24") (pintype "bidirectional"))
    )
    (net (code "86") (name "unconnected-(U$6-CDI#-Pad11)") (class "Default")
      (node (ref "U$6") (pin "11") (pinfunction "CDI#_11") (pintype "output"))
    )
    (net (code "87") (name "unconnected-(U$6-CD{slash}DAT3-Pad1)") (class "Default")
      (node (ref "U$6") (pin "1") (pinfunction "CD/DAT3_1") (pintype "bidirectional"))
    )
    (net (code "88") (name "unconnected-(U$6-CLK{slash}SCLK-Pad5)") (class "Default")
      (node (ref "U$6") (pin "5") (pinfunction "CLK/SCLK_5") (pintype "bidirectional"))
    )
    (net (code "89") (name "unconnected-(U$6-CMD{slash}DI-Pad2)") (class "Default")
      (node (ref "U$6") (pin "2") (pinfunction "CMD/DI_2") (pintype "bidirectional"))
    )
    (net (code "90") (name "unconnected-(U$6-DAT0-Pad7)") (class "Default")
      (node (ref "U$6") (pin "7") (pinfunction "DAT0_7") (pintype "bidirectional"))
    )
    (net (code "91") (name "unconnected-(U$6-DAT1-Pad8)") (class "Default")
      (node (ref "U$6") (pin "8") (pinfunction "DAT1_8") (pintype "bidirectional"))
    )
    (net (code "92") (name "unconnected-(U$6-DAT2-Pad9)") (class "Default")
      (node (ref "U$6") (pin "9") (pinfunction "DAT2_9") (pintype "bidirectional"))
    )
    (net (code "93") (name "unconnected-(U$6-WP-Pad10)") (class "Default")
      (node (ref "U$6") (pin "10") (pinfunction "WP_10") (pintype "output"))
    )
  )
)
